# 2_I_O.net
KiCad netlist of a schematic drawn in Altium Designer
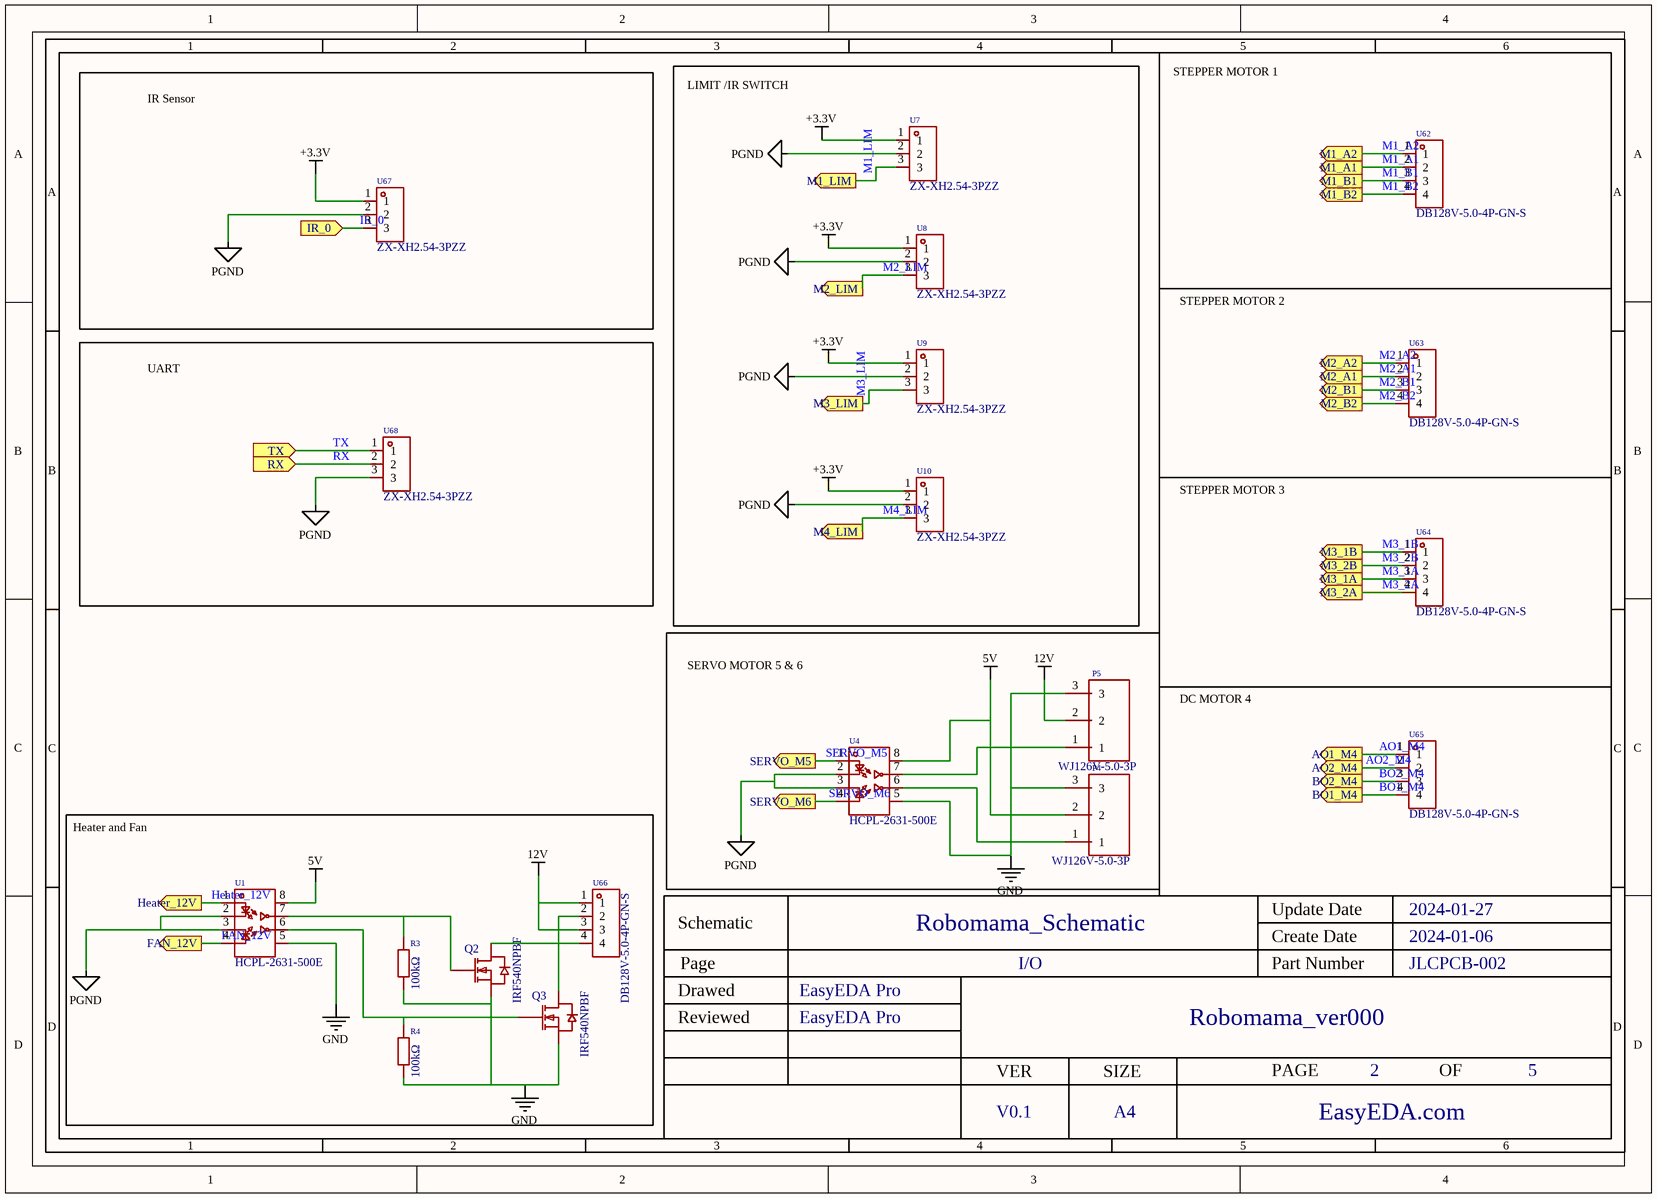
[diagram p0: 2_I_O.schdoc]

(export (version "E")
  (design (tool "Eeschema 10.0.6"))
  (components
    (comp (ref "P4")
      (value "WJ126V-5.0-3P")
      (footprint "CONN-TH_3P-P5.00_WJ126V-5.0-3P")
      (fields (field (name "MANUFACTURER") "KANGNEX(康奈克斯电气)"))
      (libsource (lib "altium-import") (part "root_2_WJ126V-5.0-3P_"))
    )
    (comp (ref "P5")
      (value "WJ126V-5.0-3P")
      (footprint "CONN-TH_3P-P5.00_WJ126V-5.0-3P")
      (fields (field (name "MANUFACTURER") "KANGNEX(康奈克斯电气)"))
      (libsource (lib "altium-import") (part "root_2_WJ126V-5.0-3P_"))
    )
    (comp (ref "Q2")
      (value "IRF540NPBF")
      (footprint "TO-220-3_L10.0-W4.5-P2.54-L")
      (fields (field (name "MANUFACTURER") "Infineon(英飞凌)"))
      (libsource (lib "altium-import") (part "root_0_IRF540NPBF_"))
    )
    (comp (ref "Q3")
      (value "IRF540NPBF")
      (footprint "TO-220-3_L10.0-W4.5-P2.54-L")
      (fields (field (name "MANUFACTURER") "Infineon(英飞凌)"))
      (libsource (lib "altium-import") (part "root_0_IRF540NPBF_"))
    )
    (comp (ref "R3")
      (value "100kΩ")
      (footprint "R0603")
      (fields
        (field (name "MANUFACTURER") "UNI-ROYAL(厚声)")
        (field (name "MANUFACTURER PART") "0603WAF1003T5E")
        (field (name "TOLERANCE") "±1%")
      )
      (libsource (lib "altium-import") (part "root_1_0603WAF1003T5E_"))
    )
    (comp (ref "R4")
      (value "100kΩ")
      (footprint "R0603")
      (fields
        (field (name "MANUFACTURER") "UNI-ROYAL(厚声)")
        (field (name "MANUFACTURER PART") "0603WAF1003T5E")
        (field (name "TOLERANCE") "±1%")
      )
      (libsource (lib "altium-import") (part "root_1_0603WAF1003T5E_"))
    )
    (comp (ref "U1")
      (value "HCPL-2631-500E")
      (footprint "OPTO-SMD-8P_L9.7-W6.4-P2.54-LS9.7-BL")
      (fields (field (name "MANUFACTURER") "Broadcom/AVAGO(安华高)"))
      (libsource (lib "altium-import") (part "root_0_HCPL-2631-500E_"))
    )
    (comp (ref "U4")
      (value "HCPL-2631-500E")
      (footprint "OPTO-SMD-8P_L9.7-W6.4-P2.54-LS9.7-BL")
      (fields (field (name "MANUFACTURER") "Broadcom/AVAGO(安华高)"))
      (libsource (lib "altium-import") (part "root_0_HCPL-2631-500E_"))
    )
    (comp (ref "U7")
      (value "ZX-XH2.54-3PZZ")
      (footprint "CONN-TH_3P-P2.54_2501S-3P")
      (fields (field (name "MANUFACTURER") "Megastar(兆星)"))
      (libsource (lib "altium-import") (part "root_0_ZX-XH2.54-3PZZ_"))
    )
    (comp (ref "U8")
      (value "ZX-XH2.54-3PZZ")
      (footprint "CONN-TH_3P-P2.54_2501S-3P")
      (fields (field (name "MANUFACTURER") "Megastar(兆星)"))
      (libsource (lib "altium-import") (part "root_0_ZX-XH2.54-3PZZ_"))
    )
    (comp (ref "U9")
      (value "ZX-XH2.54-3PZZ")
      (footprint "CONN-TH_3P-P2.54_2501S-3P")
      (fields (field (name "MANUFACTURER") "Megastar(兆星)"))
      (libsource (lib "altium-import") (part "root_0_ZX-XH2.54-3PZZ_"))
    )
    (comp (ref "U10")
      (value "ZX-XH2.54-3PZZ")
      (footprint "CONN-TH_3P-P2.54_2501S-3P")
      (fields (field (name "MANUFACTURER") "Megastar(兆星)"))
      (libsource (lib "altium-import") (part "root_0_ZX-XH2.54-3PZZ_"))
    )
    (comp (ref "U62")
      (value "DB128V-5.0-4P-GN-S")
      (footprint "CONN-TH_DB128V-5.0-4P")
      (fields (field (name "MANUFACTURER") "DIBO(地博电气)"))
      (libsource (lib "altium-import") (part "root_0_DB128V-5.0-4P-GN-S_"))
    )
    (comp (ref "U63")
      (value "DB128V-5.0-4P-GN-S")
      (footprint "CONN-TH_DB128V-5.0-4P")
      (fields (field (name "MANUFACTURER") "DIBO(地博电气)"))
      (libsource (lib "altium-import") (part "root_0_DB128V-5.0-4P-GN-S_"))
    )
    (comp (ref "U64")
      (value "DB128V-5.0-4P-GN-S")
      (footprint "CONN-TH_DB128V-5.0-4P")
      (fields (field (name "MANUFACTURER") "DIBO(地博电气)"))
      (libsource (lib "altium-import") (part "root_0_DB128V-5.0-4P-GN-S_"))
    )
    (comp (ref "U65")
      (value "DB128V-5.0-4P-GN-S")
      (footprint "CONN-TH_DB128V-5.0-4P")
      (fields (field (name "MANUFACTURER") "DIBO(地博电气)"))
      (libsource (lib "altium-import") (part "root_0_DB128V-5.0-4P-GN-S_"))
    )
    (comp (ref "U66")
      (value "DB128V-5.0-4P-GN-S")
      (footprint "CONN-TH_DB128V-5.0-4P")
      (fields (field (name "MANUFACTURER") "DIBO(地博电气)"))
      (libsource (lib "altium-import") (part "root_0_DB128V-5.0-4P-GN-S_"))
    )
    (comp (ref "U67")
      (value "ZX-XH2.54-3PZZ")
      (footprint "CONN-TH_3P-P2.54_2501S-3P")
      (fields (field (name "MANUFACTURER") "Megastar(兆星)"))
      (libsource (lib "altium-import") (part "root_0_ZX-XH2.54-3PZZ_"))
    )
    (comp (ref "U68")
      (value "ZX-XH2.54-3PZZ")
      (footprint "CONN-TH_3P-P2.54_2501S-3P")
      (fields (field (name "MANUFACTURER") "Megastar(兆星)"))
      (libsource (lib "altium-import") (part "root_0_ZX-XH2.54-3PZZ_"))
    )
  )
  (nets
    (net (code "1") (name "+3.3V") (class "Default")
      (node (ref "U10") (pin "1") (pinfunction "1_1") (pintype "passive"))
      (node (ref "U67") (pin "1") (pinfunction "1_1") (pintype "passive"))
      (node (ref "U7") (pin "1") (pinfunction "1_1") (pintype "passive"))
      (node (ref "U8") (pin "1") (pinfunction "1_1") (pintype "passive"))
      (node (ref "U9") (pin "1") (pinfunction "1_1") (pintype "passive"))
    )
    (net (code "2") (name "/AO1_M4") (class "Default")
      (node (ref "U65") (pin "1") (pinfunction "1_1") (pintype "passive"))
    )
    (net (code "3") (name "/AO2_M4") (class "Default")
      (node (ref "U65") (pin "2") (pinfunction "2_2") (pintype "passive"))
    )
    (net (code "4") (name "/BO1_M4") (class "Default")
      (node (ref "U65") (pin "4") (pinfunction "4_4") (pintype "passive"))
    )
    (net (code "5") (name "/BO2_M4") (class "Default")
      (node (ref "U65") (pin "3") (pinfunction "3_3") (pintype "passive"))
    )
    (net (code "6") (name "/FAN_12V") (class "Default")
      (node (ref "U1") (pin "4") (pinfunction "ANODE_2_4") (pintype "passive"))
    )
    (net (code "7") (name "/Heater_12V") (class "Default")
      (node (ref "U1") (pin "1") (pinfunction "ANODE_1_1") (pintype "passive"))
    )
    (net (code "8") (name "/IR_0") (class "Default")
      (node (ref "U67") (pin "3") (pinfunction "3_3") (pintype "passive"))
    )
    (net (code "9") (name "/M1_A1") (class "Default")
      (node (ref "U62") (pin "2") (pinfunction "2_2") (pintype "passive"))
    )
    (net (code "10") (name "/M1_A2") (class "Default")
      (node (ref "U62") (pin "1") (pinfunction "1_1") (pintype "passive"))
    )
    (net (code "11") (name "/M1_B1") (class "Default")
      (node (ref "U62") (pin "3") (pinfunction "3_3") (pintype "passive"))
    )
    (net (code "12") (name "/M1_B2") (class "Default")
      (node (ref "U62") (pin "4") (pinfunction "4_4") (pintype "passive"))
    )
    (net (code "13") (name "/M1_LIM") (class "Default")
      (node (ref "U7") (pin "3") (pinfunction "3_3") (pintype "passive"))
    )
    (net (code "14") (name "/M2_A1") (class "Default")
      (node (ref "U63") (pin "2") (pinfunction "2_2") (pintype "passive"))
    )
    (net (code "15") (name "/M2_A2") (class "Default")
      (node (ref "U63") (pin "1") (pinfunction "1_1") (pintype "passive"))
    )
    (net (code "16") (name "/M2_B1") (class "Default")
      (node (ref "U63") (pin "3") (pinfunction "3_3") (pintype "passive"))
    )
    (net (code "17") (name "/M2_B2") (class "Default")
      (node (ref "U63") (pin "4") (pinfunction "4_4") (pintype "passive"))
    )
    (net (code "18") (name "/M2_LIM") (class "Default")
      (node (ref "U8") (pin "3") (pinfunction "3_3") (pintype "passive"))
    )
    (net (code "19") (name "/M3_1A") (class "Default")
      (node (ref "U64") (pin "3") (pinfunction "3_3") (pintype "passive"))
    )
    (net (code "20") (name "/M3_1B") (class "Default")
      (node (ref "U64") (pin "1") (pinfunction "1_1") (pintype "passive"))
    )
    (net (code "21") (name "/M3_2A") (class "Default")
      (node (ref "U64") (pin "4") (pinfunction "4_4") (pintype "passive"))
    )
    (net (code "22") (name "/M3_2B") (class "Default")
      (node (ref "U64") (pin "2") (pinfunction "2_2") (pintype "passive"))
    )
    (net (code "23") (name "/M3_LIM") (class "Default")
      (node (ref "U9") (pin "3") (pinfunction "3_3") (pintype "passive"))
    )
    (net (code "24") (name "/M4_LIM") (class "Default")
      (node (ref "U10") (pin "3") (pinfunction "3_3") (pintype "passive"))
    )
    (net (code "25") (name "/RX") (class "Default")
      (node (ref "U68") (pin "2") (pinfunction "2_2") (pintype "passive"))
    )
    (net (code "26") (name "/SERVO_M5") (class "Default")
      (node (ref "U4") (pin "1") (pinfunction "ANODE_1_1") (pintype "passive"))
    )
    (net (code "27") (name "/SERVO_M6") (class "Default")
      (node (ref "U4") (pin "4") (pinfunction "ANODE_2_4") (pintype "passive"))
    )
    (net (code "28") (name "/TX") (class "Default")
      (node (ref "U68") (pin "1") (pinfunction "1_1") (pintype "passive"))
    )
    (net (code "29") (name "5V") (class "Default")
      (node (ref "P4") (pin "2") (pinfunction "2_2") (pintype "passive"))
      (node (ref "U1") (pin "8") (pinfunction "VCC_8") (pintype "passive"))
      (node (ref "U4") (pin "8") (pinfunction "VCC_8") (pintype "passive"))
    )
    (net (code "30") (name "12V") (class "Default")
      (node (ref "P5") (pin "2") (pinfunction "2_2") (pintype "passive"))
      (node (ref "U66") (pin "1") (pinfunction "1_1") (pintype "passive"))
      (node (ref "U66") (pin "3") (pinfunction "3_3") (pintype "passive"))
    )
    (net (code "31") (name "GND") (class "Default")
      (node (ref "P4") (pin "3") (pinfunction "3_3") (pintype "passive"))
      (node (ref "P5") (pin "3") (pinfunction "3_3") (pintype "passive"))
      (node (ref "Q2") (pin "3") (pinfunction "S_3") (pintype "passive"))
      (node (ref "Q3") (pin "3") (pinfunction "S_3") (pintype "passive"))
      (node (ref "R3") (pin "1") (pinfunction "1_1") (pintype "passive"))
      (node (ref "R4") (pin "1") (pinfunction "1_1") (pintype "passive"))
      (node (ref "U1") (pin "5") (pinfunction "GND_5") (pintype "passive"))
      (node (ref "U4") (pin "5") (pinfunction "GND_5") (pintype "passive"))
    )
    (net (code "32") (name "Net-(Q2-D)") (class "Default")
      (node (ref "Q2") (pin "2") (pinfunction "D_2") (pintype "passive"))
      (node (ref "U66") (pin "4") (pinfunction "4_4") (pintype "passive"))
    )
    (net (code "33") (name "Net-(Q2-G)") (class "Default")
      (node (ref "Q2") (pin "1") (pinfunction "G_1") (pintype "passive"))
      (node (ref "R3") (pin "2") (pinfunction "2_2") (pintype "passive"))
      (node (ref "U1") (pin "7") (pinfunction "VO1_7") (pintype "passive"))
    )
    (net (code "34") (name "Net-(Q3-D)") (class "Default")
      (node (ref "Q3") (pin "2") (pinfunction "D_2") (pintype "passive"))
      (node (ref "U66") (pin "2") (pinfunction "2_2") (pintype "passive"))
    )
    (net (code "35") (name "Net-(Q3-G)") (class "Default")
      (node (ref "Q3") (pin "1") (pinfunction "G_1") (pintype "passive"))
      (node (ref "R4") (pin "2") (pinfunction "2_2") (pintype "passive"))
      (node (ref "U1") (pin "6") (pinfunction "VO2_6") (pintype "passive"))
    )
    (net (code "36") (name "Net-(U4-VO1)") (class "Default")
      (node (ref "P5") (pin "1") (pinfunction "1_1") (pintype "passive"))
      (node (ref "U4") (pin "7") (pinfunction "VO1_7") (pintype "passive"))
    )
    (net (code "37") (name "Net-(U4-VO2)") (class "Default")
      (node (ref "P4") (pin "1") (pinfunction "1_1") (pintype "passive"))
      (node (ref "U4") (pin "6") (pinfunction "VO2_6") (pintype "passive"))
    )
    (net (code "38") (name "PGND") (class "Default")
      (node (ref "U1") (pin "2") (pinfunction "CATHODE_1_2") (pintype "passive"))
      (node (ref "U1") (pin "3") (pinfunction "CATHODE_2_3") (pintype "passive"))
      (node (ref "U10") (pin "2") (pinfunction "2_2") (pintype "passive"))
      (node (ref "U4") (pin "2") (pinfunction "CATHODE_1_2") (pintype "passive"))
      (node (ref "U4") (pin "3") (pinfunction "CATHODE_2_3") (pintype "passive"))
      (node (ref "U67") (pin "2") (pinfunction "2_2") (pintype "passive"))
      (node (ref "U68") (pin "3") (pinfunction "3_3") (pintype "passive"))
      (node (ref "U7") (pin "2") (pinfunction "2_2") (pintype "passive"))
      (node (ref "U8") (pin "2") (pinfunction "2_2") (pintype "passive"))
      (node (ref "U9") (pin "2") (pinfunction "2_2") (pintype "passive"))
    )
  )
)
